# MotorBoardDev.net
KiCad netlist of a schematic drawn in EAGLE
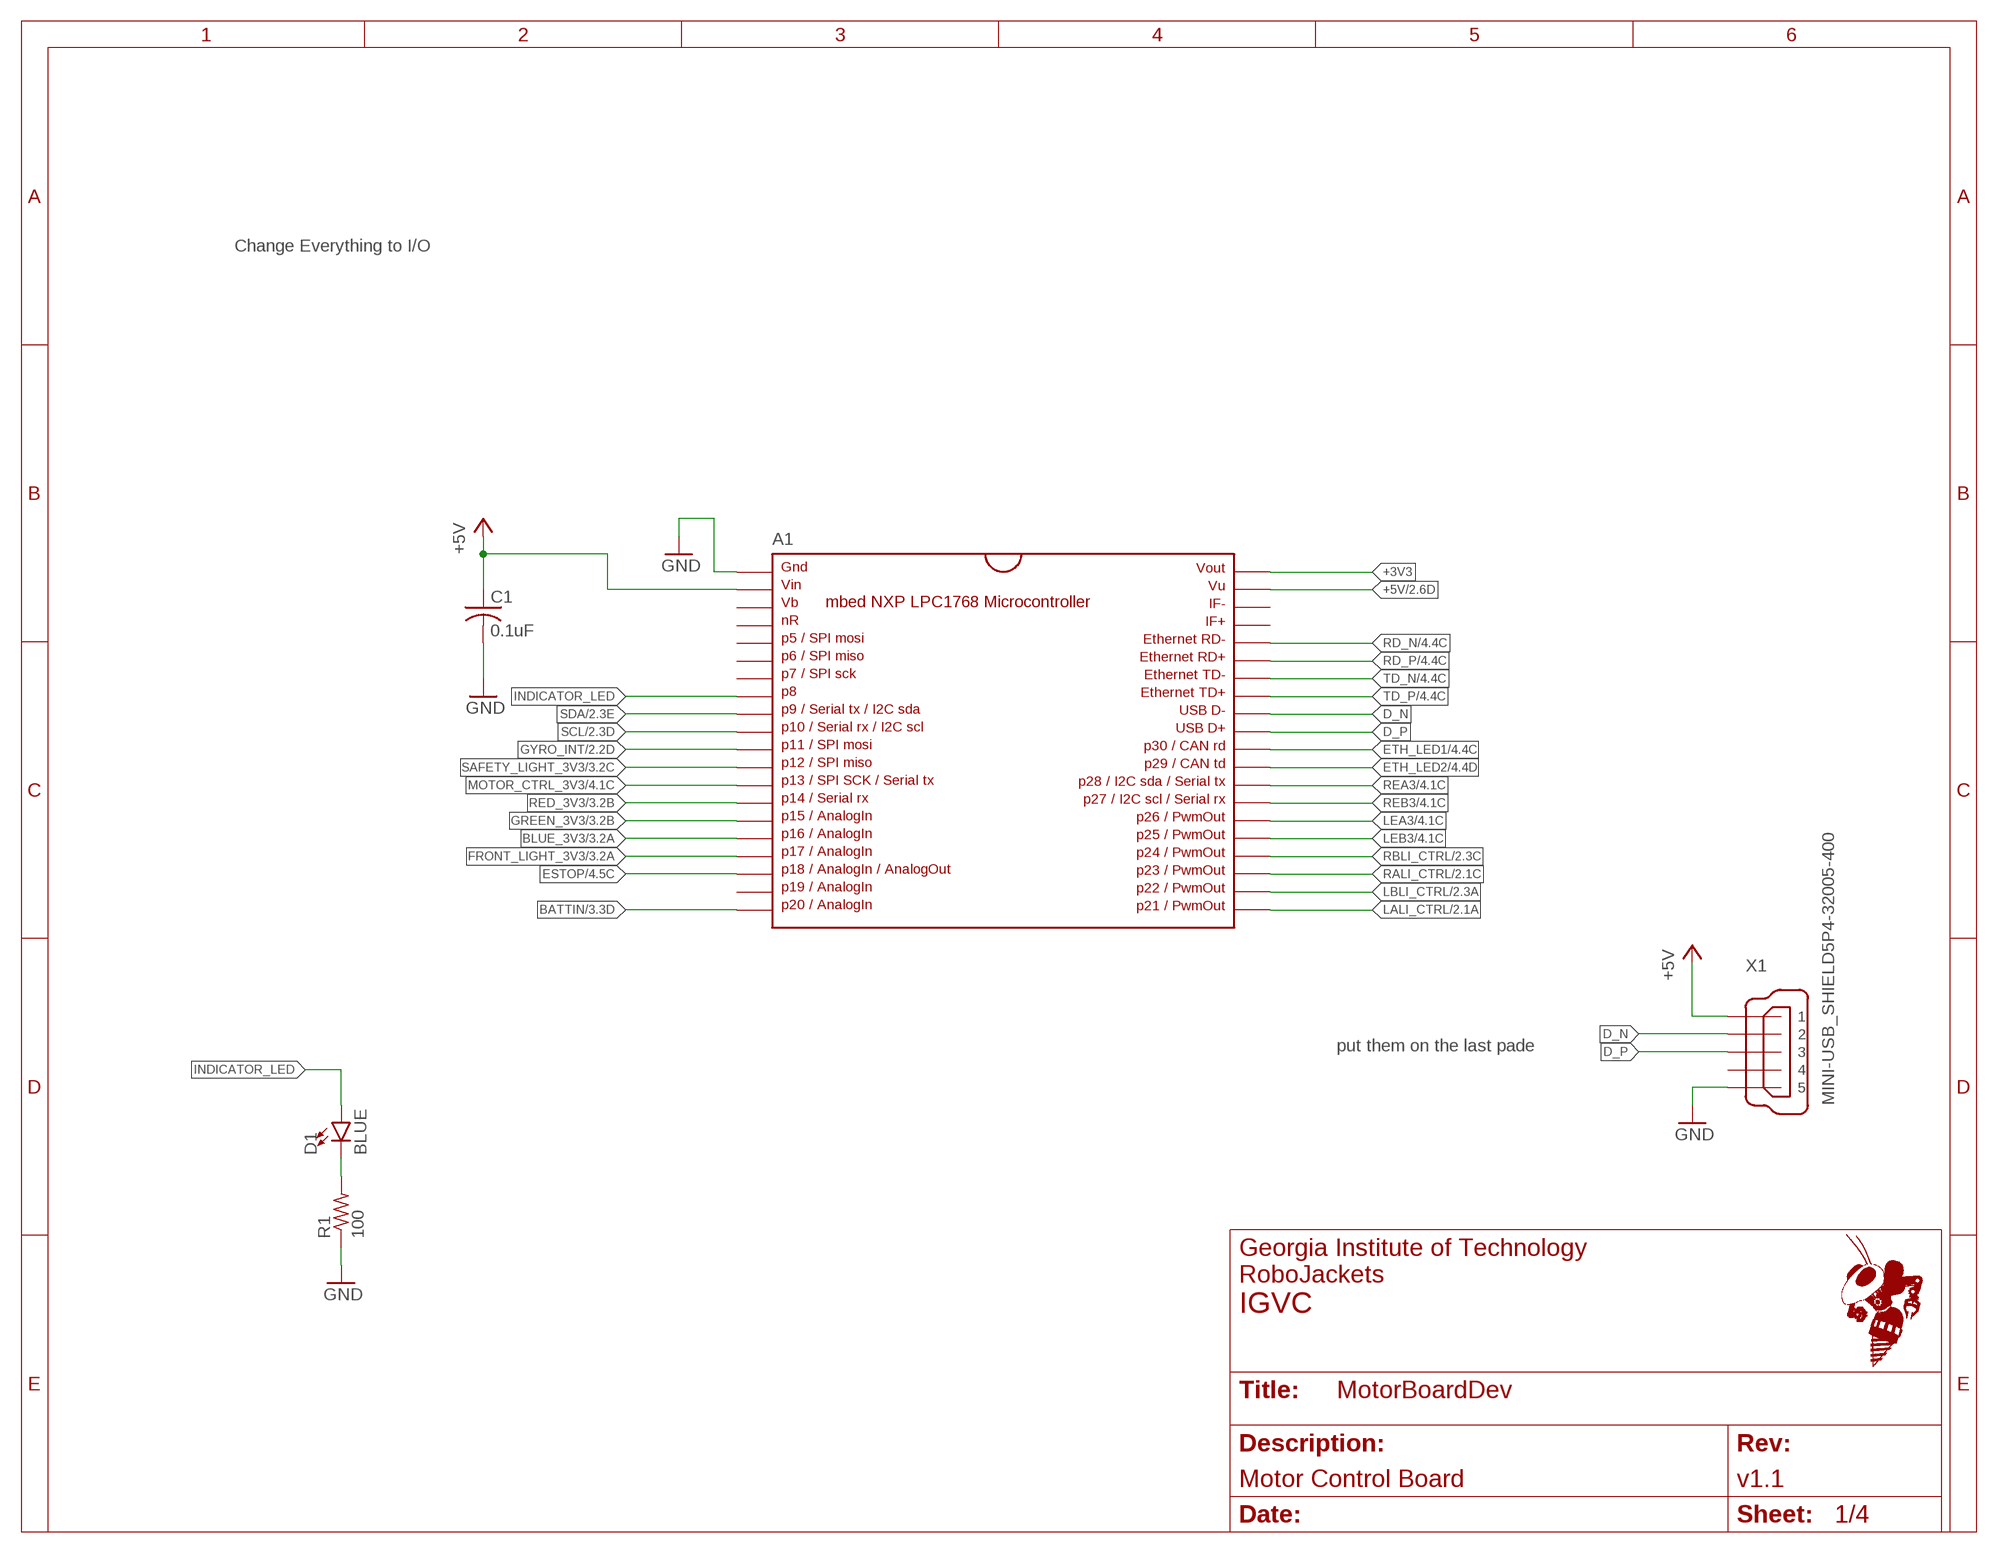
[diagram p0: schematic, sheet 1]
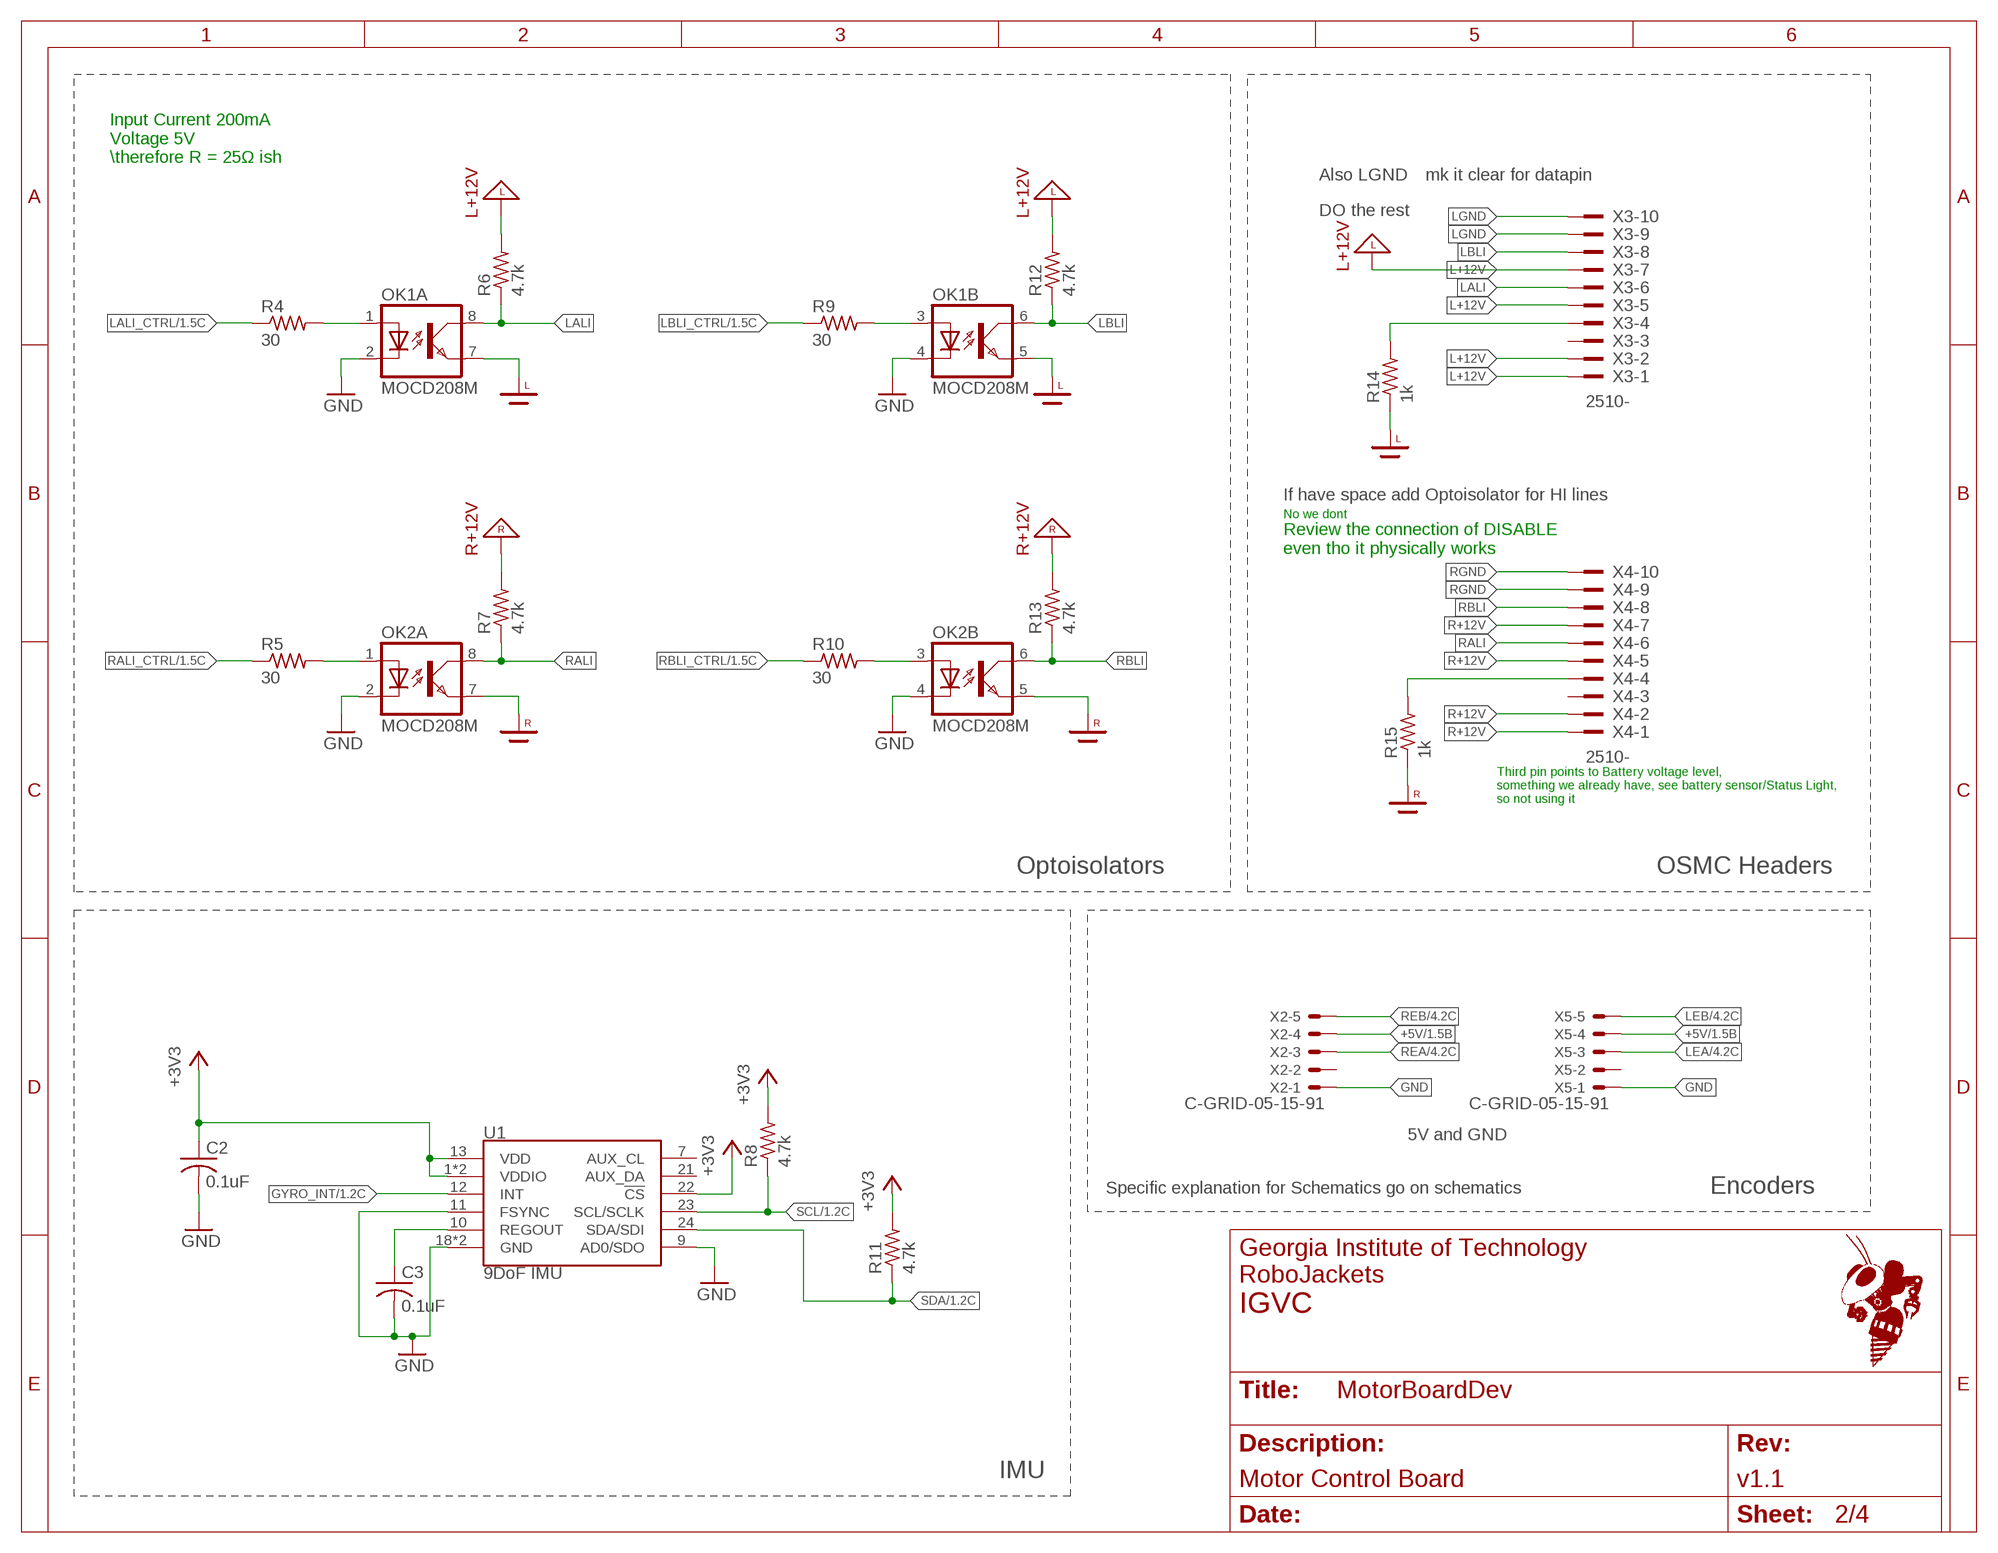
[diagram p1: schematic, sheet 2]
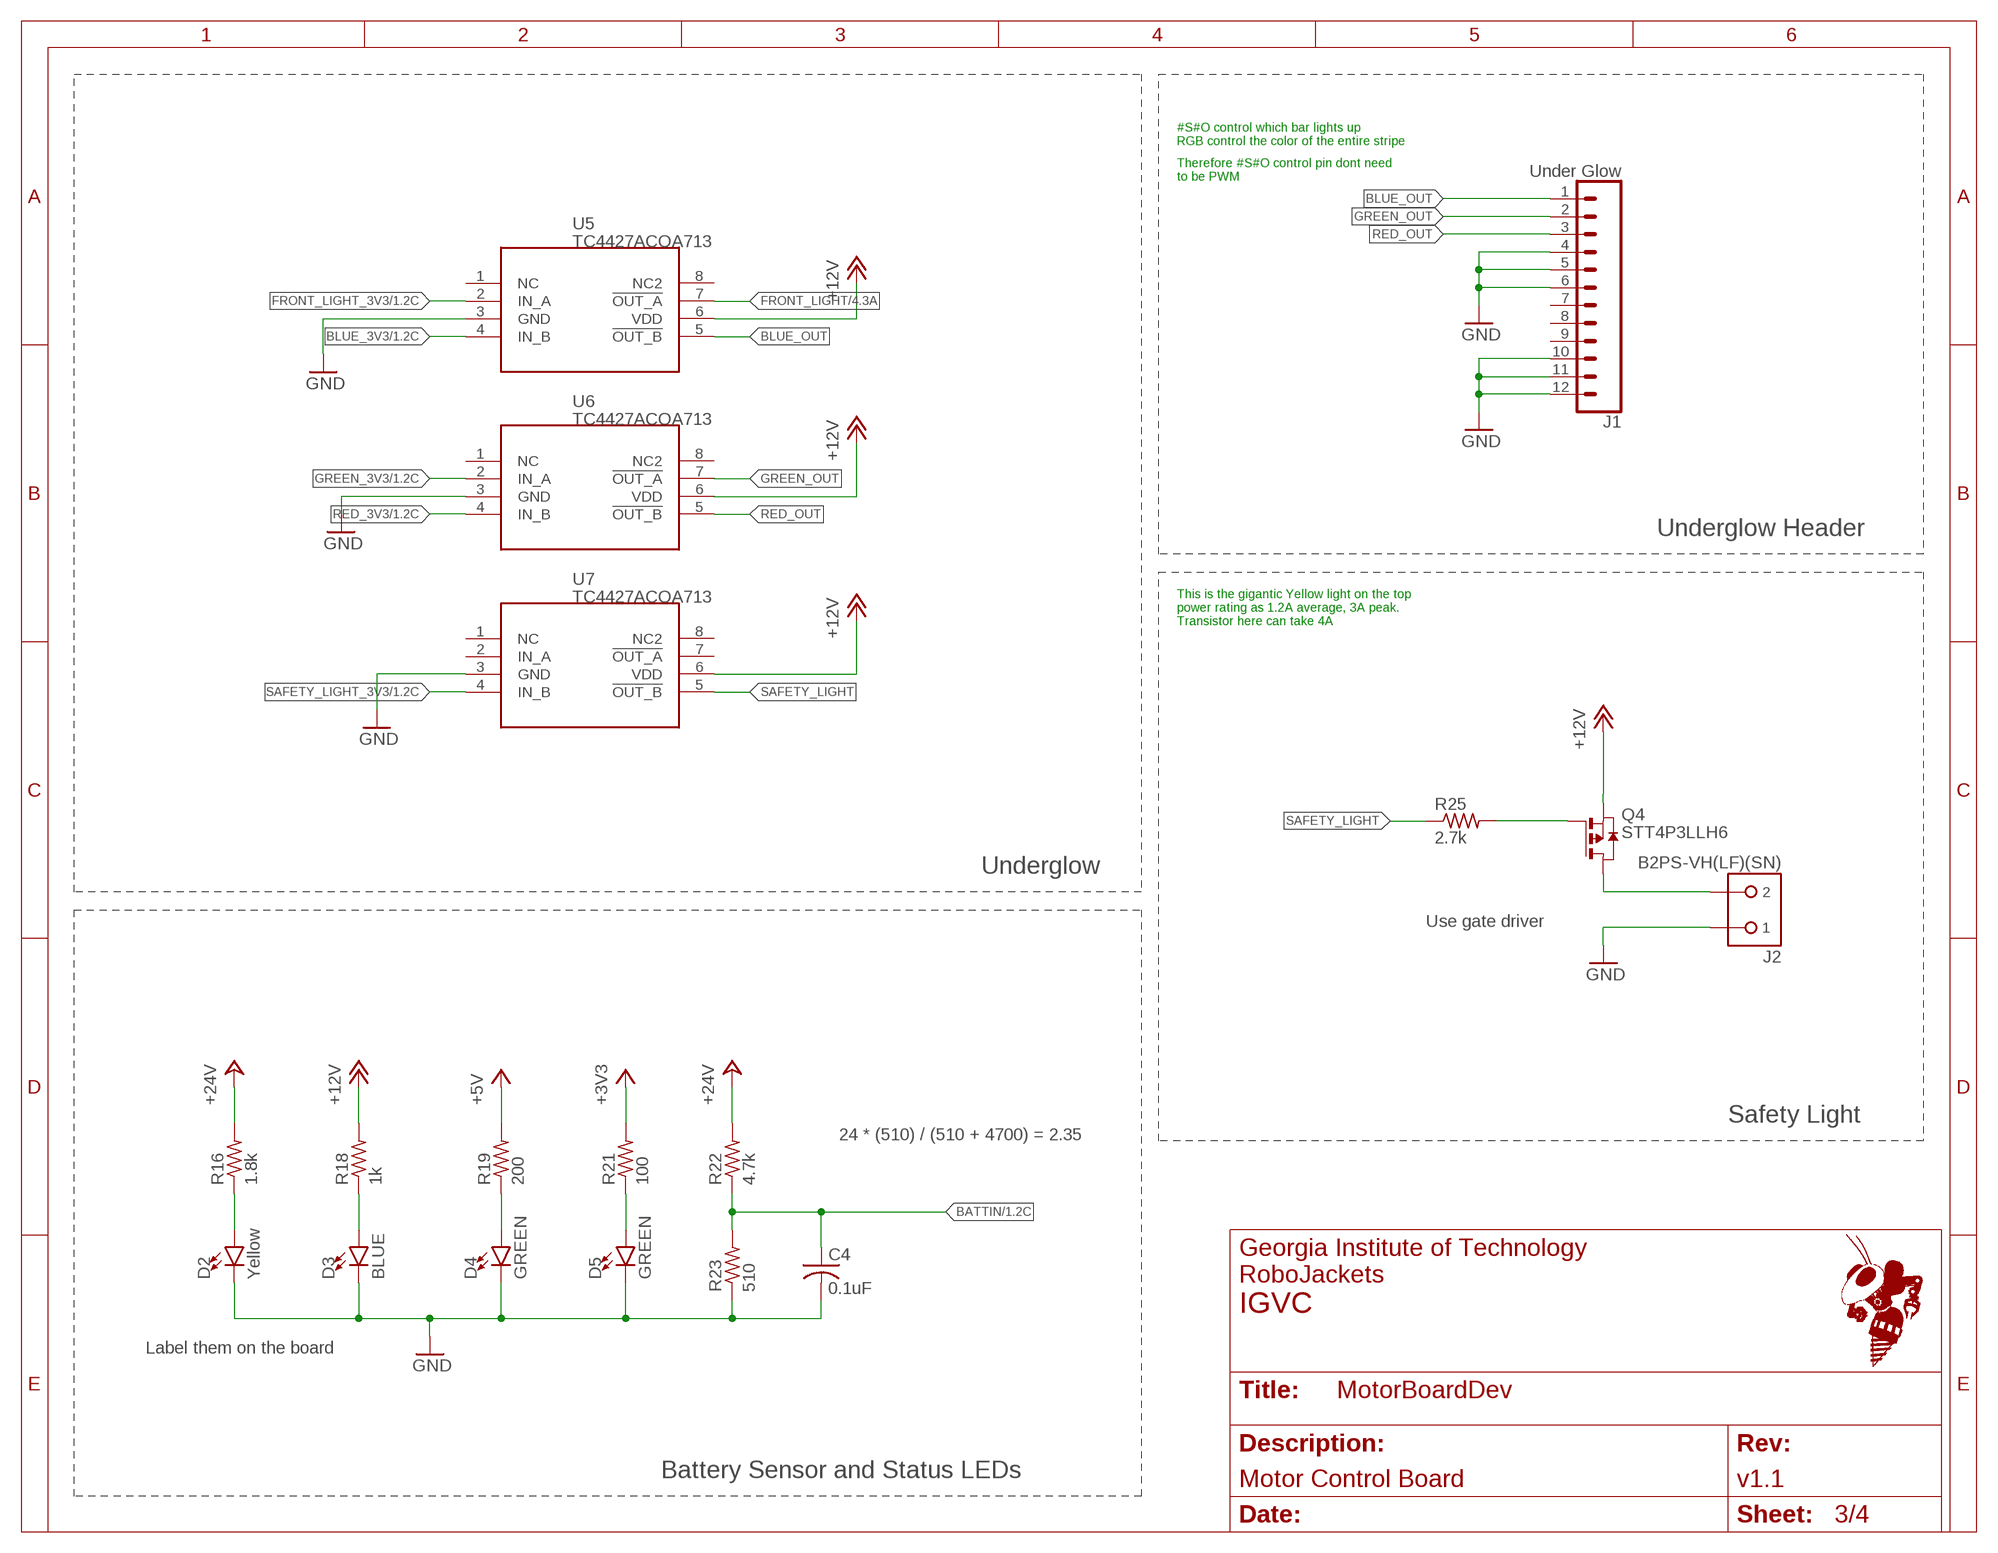
[diagram p2: schematic, sheet 3]
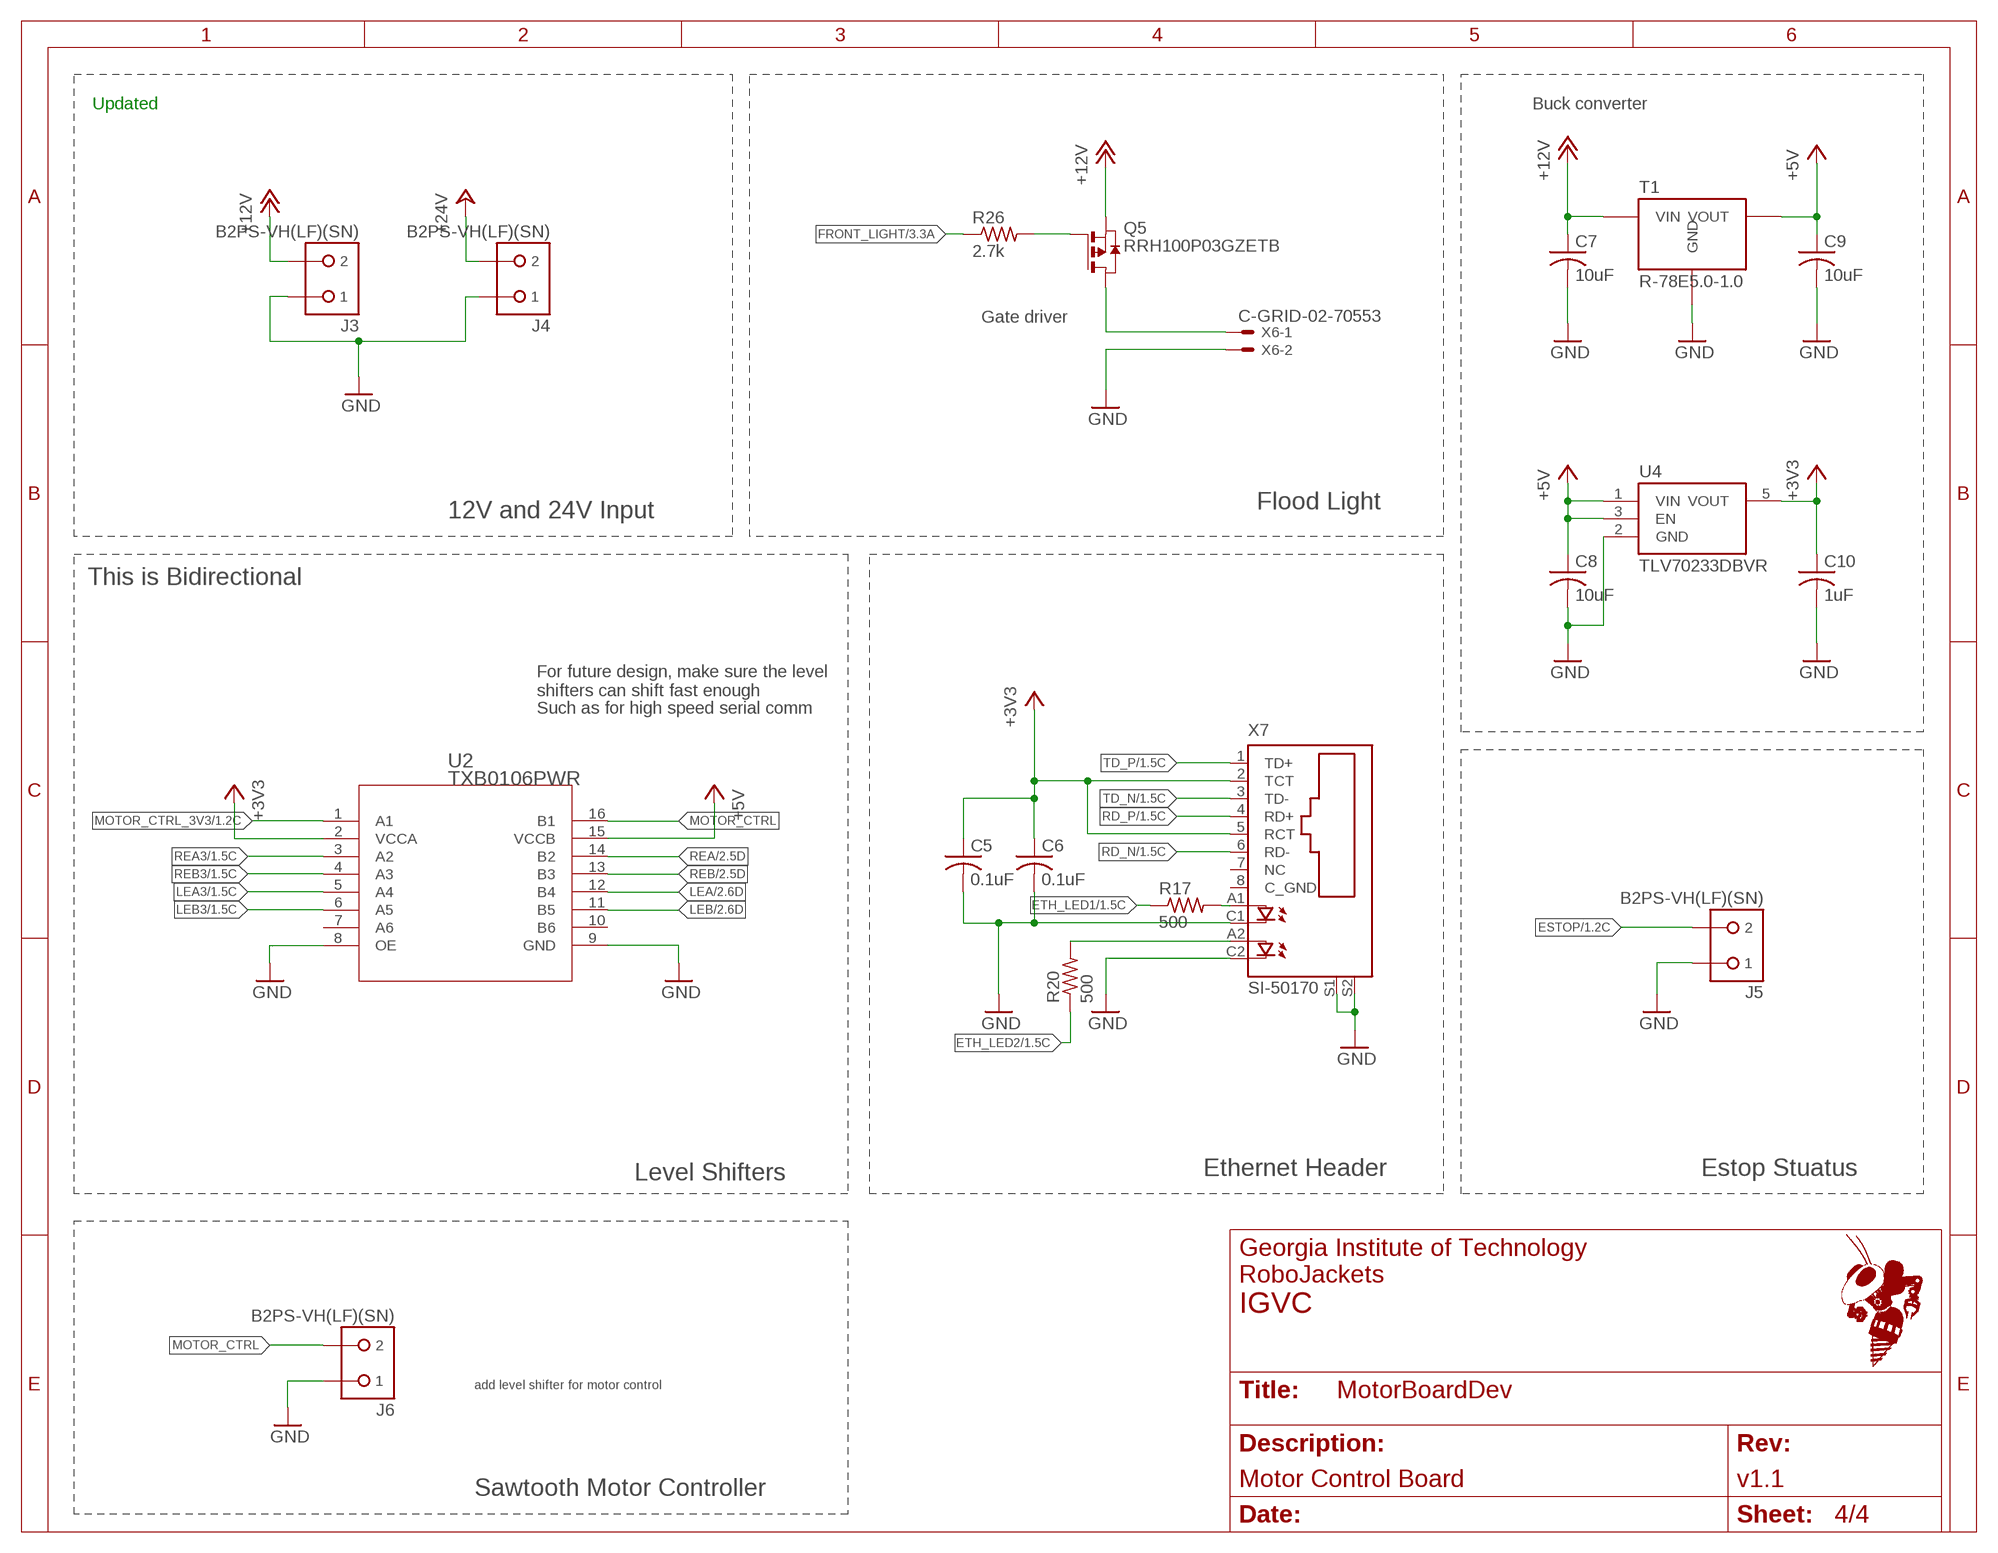
[diagram p3: schematic, sheet 4]

(export (version "E")
  (design (tool "Eeschema 10.0.6"))
  (components
    (comp (ref "A1")
      (value "MBED1768")
      (footprint "eagle-import:SPARKFUN-BOARDS_DIL40_0.9")
      (libsource (lib "eagle-import") (part "SPARKFUN-BOARDS_MBED_NXP_LPC1768"))
    )
    (comp (ref "C1")
      (value "0.1uF")
      (footprint "eagle-import:C0603")
      (libsource (lib "eagle-import") (part "C-USC0603"))
    )
    (comp (ref "D1")
      (value "BLUE")
      (footprint "eagle-import:LED-0603")
      (libsource (lib "eagle-import") (part "LED-BLUE0603"))
    )
    (comp (ref "R1")
      (value "100")
      (footprint "eagle-import:R0603")
      (libsource (lib "eagle-import") (part "R-US_R0603"))
    )
    (comp (ref "X1")
      (value "MINI-USB_SHIELD5P4-32005-400")
      (footprint "eagle-import:32005-400")
      (libsource (lib "eagle-import") (part "MINI-USB_SHIELD5P4-32005-400"))
    )
    (comp (ref "C2")
      (value "0.1uF")
      (footprint "eagle-import:C0603")
      (libsource (lib "eagle-import") (part "C-USC0603"))
    )
    (comp (ref "C3")
      (value "0.1uF")
      (footprint "eagle-import:C0603")
      (libsource (lib "eagle-import") (part "C-USC0603"))
    )
    (comp (ref "OK1")
      (value "MOCD208M")
      (footprint "eagle-import:SOIC08-FAIRCHILD")
      (fields (field (name "MF") "FAIRCHILD SEMICONDUCTOR"))
      (libsource (lib "eagle-import") (part "MOCD20M8"))
    )
    (comp (ref "OK2")
      (value "MOCD208M")
      (footprint "eagle-import:SOIC08-FAIRCHILD")
      (fields (field (name "MF") "FAIRCHILD SEMICONDUCTOR"))
      (libsource (lib "eagle-import") (part "MOCD20M8"))
    )
    (comp (ref "R4")
      (value "30")
      (footprint "eagle-import:R0603")
      (libsource (lib "eagle-import") (part "R-US_R0603"))
    )
    (comp (ref "R5")
      (value "30")
      (footprint "eagle-import:R0603")
      (libsource (lib "eagle-import") (part "R-US_R0603"))
    )
    (comp (ref "R6")
      (value "4.7k")
      (footprint "eagle-import:R0603")
      (libsource (lib "eagle-import") (part "R-US_R0603"))
    )
    (comp (ref "R7")
      (value "4.7k")
      (footprint "eagle-import:R0603")
      (libsource (lib "eagle-import") (part "R-US_R0603"))
    )
    (comp (ref "R8")
      (value "4.7k")
      (footprint "eagle-import:R0603")
      (libsource (lib "eagle-import") (part "R-US_R0603"))
    )
    (comp (ref "R9")
      (value "30")
      (footprint "eagle-import:R0603")
      (libsource (lib "eagle-import") (part "R-US_R0603"))
    )
    (comp (ref "R10")
      (value "30")
      (footprint "eagle-import:R0603")
      (libsource (lib "eagle-import") (part "R-US_R0603"))
    )
    (comp (ref "R11")
      (value "4.7k")
      (footprint "eagle-import:R0603")
      (libsource (lib "eagle-import") (part "R-US_R0603"))
    )
    (comp (ref "R12")
      (value "4.7k")
      (footprint "eagle-import:R0603")
      (libsource (lib "eagle-import") (part "R-US_R0603"))
    )
    (comp (ref "R13")
      (value "4.7k")
      (footprint "eagle-import:R0603")
      (libsource (lib "eagle-import") (part "R-US_R0603"))
    )
    (comp (ref "R14")
      (value "1k")
      (footprint "eagle-import:R0603")
      (libsource (lib "eagle-import") (part "R-US_R0603"))
    )
    (comp (ref "R15")
      (value "1k")
      (footprint "eagle-import:R0603")
      (libsource (lib "eagle-import") (part "R-US_R0603"))
    )
    (comp (ref "U1")
      (value "9DoF IMU")
      (footprint "eagle-import:QFN24-3X3")
      (libsource (lib "eagle-import") (part "MPU-9250"))
    )
    (comp (ref "X2")
      (value "C-GRID-05-15-91")
      (footprint "eagle-import:15-91-05")
      (libsource (lib "eagle-import") (part "C-GRID-05-15-91"))
    )
    (comp (ref "X3")
      (value "2510-")
      (footprint "eagle-import:PAK100_2500-10")
      (fields (field (name "MF") "3M") (field (name "MPN") "2510-6002UB"))
      (libsource (lib "eagle-import") (part "2510-"))
    )
    (comp (ref "X4")
      (value "2510-")
      (footprint "eagle-import:PAK100_2500-10")
      (fields (field (name "MF") "3M") (field (name "MPN") "2510-6002UB"))
      (libsource (lib "eagle-import") (part "2510-"))
    )
    (comp (ref "X5")
      (value "C-GRID-05-15-91")
      (footprint "eagle-import:15-91-05")
      (libsource (lib "eagle-import") (part "C-GRID-05-15-91"))
    )
    (comp (ref "C5")
      (value "0.1uF")
      (footprint "eagle-import:C0603")
      (libsource (lib "eagle-import") (part "C-USC0603"))
    )
    (comp (ref "C6")
      (value "0.1uF")
      (footprint "eagle-import:C0603")
      (libsource (lib "eagle-import") (part "C-USC0603"))
    )
    (comp (ref "C7")
      (value "10uF")
      (footprint "eagle-import:C0805")
      (libsource (lib "eagle-import") (part "C-USC0805"))
    )
    (comp (ref "C8")
      (value "10uF")
      (footprint "eagle-import:C0805")
      (libsource (lib "eagle-import") (part "C-USC0805"))
    )
    (comp (ref "C9")
      (value "10uF")
      (footprint "eagle-import:C0805")
      (libsource (lib "eagle-import") (part "C-USC0805"))
    )
    (comp (ref "C10")
      (value "1uF")
      (footprint "eagle-import:C0805")
      (libsource (lib "eagle-import") (part "C-USC0805"))
    )
    (comp (ref "J3")
      (value "B2PS-VH(LF)(SN)")
      (footprint "eagle-import:B2PS-CENTERED")
      (libsource (lib "eagle-import") (part "B2P?-VH(LF)(SN)S"))
    )
    (comp (ref "J4")
      (value "B2PS-VH(LF)(SN)")
      (footprint "eagle-import:B2PS-CENTERED")
      (libsource (lib "eagle-import") (part "B2P?-VH(LF)(SN)S"))
    )
    (comp (ref "J5")
      (value "B2PS-VH(LF)(SN)")
      (footprint "eagle-import:B2PS-CENTERED")
      (libsource (lib "eagle-import") (part "B2P?-VH(LF)(SN)S"))
    )
    (comp (ref "J6")
      (value "B2PS-VH(LF)(SN)")
      (footprint "eagle-import:B2PS-CENTERED")
      (libsource (lib "eagle-import") (part "B2P?-VH(LF)(SN)S"))
    )
    (comp (ref "Q5")
      (value "RRH100P03GZETB")
      (footprint "eagle-import:SOIC-8")
      (libsource (lib "eagle-import") (part "RRH100P03GZETB"))
    )
    (comp (ref "R17")
      (value "500")
      (footprint "eagle-import:R0603")
      (libsource (lib "eagle-import") (part "R-US_R0603"))
    )
    (comp (ref "R20")
      (value "500")
      (footprint "eagle-import:R0603")
      (libsource (lib "eagle-import") (part "R-US_R0603"))
    )
    (comp (ref "R26")
      (value "2.7k")
      (footprint "eagle-import:R0603")
      (libsource (lib "eagle-import") (part "R-US_R0603"))
    )
    (comp (ref "T1")
      (value "R-78E5.0-1.0")
      (footprint "eagle-import:R-78E")
      (libsource (lib "eagle-import") (part "R-78E5.0-1.0"))
    )
    (comp (ref "U2")
      (value "TXB0106PWR")
      (footprint "eagle-import:PW16")
      (libsource (lib "eagle-import") (part "TXB0106PWR"))
    )
    (comp (ref "U4")
      (value "TLV70233DBVR")
      (footprint "eagle-import:SOT-23-5")
      (libsource (lib "eagle-import") (part "TLV70233DBVR"))
    )
    (comp (ref "X6")
      (value "C-GRID-02-70553")
      (footprint "eagle-import:70553-02")
      (libsource (lib "eagle-import") (part "C-GRID-02-70553"))
    )
    (comp (ref "X7")
      (value "SI-50170")
      (footprint "eagle-import:SI-50170")
      (libsource (lib "eagle-import") (part "SI-50170"))
    )
    (comp (ref "C4")
      (value "0.1uF")
      (footprint "eagle-import:C0603")
      (libsource (lib "eagle-import") (part "C-USC0603"))
    )
    (comp (ref "D2")
      (value "Yellow")
      (footprint "eagle-import:LED-0603")
      (libsource (lib "eagle-import") (part "LED-YELLOW0603"))
    )
    (comp (ref "D3")
      (value "BLUE")
      (footprint "eagle-import:LED-0603")
      (libsource (lib "eagle-import") (part "LED-BLUE0603"))
    )
    (comp (ref "D4")
      (value "GREEN")
      (footprint "eagle-import:LED-0603")
      (libsource (lib "eagle-import") (part "LED-GREEN0603"))
    )
    (comp (ref "D5")
      (value "GREEN")
      (footprint "eagle-import:LED-0603")
      (libsource (lib "eagle-import") (part "LED-GREEN0603"))
    )
    (comp (ref "J1")
      (value "Under Glow")
      (footprint "eagle-import:1X12_LOCK_LONGPADS")
      (libsource (lib "eagle-import") (part "CONN_12LOCK_LONGPADS"))
    )
    (comp (ref "J2")
      (value "B2PS-VH(LF)(SN)")
      (footprint "eagle-import:B2PS-CENTERED")
      (libsource (lib "eagle-import") (part "B2P?-VH(LF)(SN)S"))
    )
    (comp (ref "Q4")
      (value "STT4P3LLH6")
      (footprint "eagle-import:SOT23-6")
      (libsource (lib "eagle-import") (part "STT4P3LLH6"))
    )
    (comp (ref "R16")
      (value "1.8k")
      (footprint "eagle-import:R0603")
      (libsource (lib "eagle-import") (part "R-US_R0603"))
    )
    (comp (ref "R18")
      (value "1k")
      (footprint "eagle-import:R0603")
      (libsource (lib "eagle-import") (part "R-US_R0603"))
    )
    (comp (ref "R19")
      (value "200")
      (footprint "eagle-import:R0603")
      (libsource (lib "eagle-import") (part "R-US_R0603"))
    )
    (comp (ref "R21")
      (value "100")
      (footprint "eagle-import:R0603")
      (libsource (lib "eagle-import") (part "R-US_R0603"))
    )
    (comp (ref "R22")
      (value "4.7k")
      (footprint "eagle-import:R0603")
      (libsource (lib "eagle-import") (part "R-US_R0603"))
    )
    (comp (ref "R23")
      (value "510")
      (footprint "eagle-import:R0603")
      (libsource (lib "eagle-import") (part "R-US_R0603"))
    )
    (comp (ref "R25")
      (value "2.7k")
      (footprint "eagle-import:R0603")
      (libsource (lib "eagle-import") (part "R-US_R0603"))
    )
    (comp (ref "U5")
      (value "TC4427ACOA713")
      (footprint "eagle-import:SOIC-8")
      (libsource (lib "eagle-import") (part "TC4427ACOA713"))
    )
    (comp (ref "U6")
      (value "TC4427ACOA713")
      (footprint "eagle-import:SOIC-8")
      (libsource (lib "eagle-import") (part "TC4427ACOA713"))
    )
    (comp (ref "U7")
      (value "TC4427ACOA713")
      (footprint "eagle-import:SOIC-8")
      (libsource (lib "eagle-import") (part "TC4427ACOA713"))
    )
  )
  (nets
    (net (code "1") (name "+3V3") (class "Default")
      (node (ref "A1") (pin "40") (pinfunction "P$40_40") (pintype "bidirectional"))
      (node (ref "C10") (pin "1") (pinfunction "1_1") (pintype "passive"))
      (node (ref "C2") (pin "1") (pinfunction "1_1") (pintype "passive"))
      (node (ref "C5") (pin "1") (pinfunction "1_1") (pintype "passive"))
      (node (ref "C6") (pin "1") (pinfunction "1_1") (pintype "passive"))
      (node (ref "R11") (pin "2") (pinfunction "2_2") (pintype "passive"))
      (node (ref "R21") (pin "2") (pinfunction "2_2") (pintype "passive"))
      (node (ref "R8") (pin "2") (pinfunction "2_2") (pintype "passive"))
      (node (ref "U1") (pin "1") (pinfunction "VDDIO_1") (pintype "bidirectional"))
      (node (ref "U1") (pin "13") (pinfunction "VDD_13") (pintype "bidirectional"))
      (node (ref "U1") (pin "22") (pinfunction "~{CS}_22") (pintype "bidirectional"))
      (node (ref "U1") (pin "8") (pinfunction "VDDIO_8") (pintype "bidirectional"))
      (node (ref "U2") (pin "2") (pinfunction "VCCA_2") (pintype "power_in"))
      (node (ref "U4") (pin "5") (pinfunction "VOUT_5") (pintype "bidirectional"))
      (node (ref "X7") (pin "2") (pinfunction "TCT_2") (pintype "passive"))
      (node (ref "X7") (pin "5") (pinfunction "RCT_5") (pintype "passive"))
    )
    (net (code "2") (name "+5V") (class "Default")
      (node (ref "A1") (pin "2") (pinfunction "P$2_2") (pintype "bidirectional"))
      (node (ref "A1") (pin "39") (pinfunction "P$39_39") (pintype "bidirectional"))
      (node (ref "C1") (pin "1") (pinfunction "1_1") (pintype "passive"))
      (node (ref "C8") (pin "1") (pinfunction "1_1") (pintype "passive"))
      (node (ref "C9") (pin "1") (pinfunction "1_1") (pintype "passive"))
      (node (ref "R19") (pin "2") (pinfunction "2_2") (pintype "passive"))
      (node (ref "T1") (pin "3") (pinfunction "VOUT_3") (pintype "bidirectional"))
      (node (ref "U2") (pin "15") (pinfunction "VCCB_15") (pintype "power_in"))
      (node (ref "U4") (pin "1") (pinfunction "VIN_1") (pintype "bidirectional"))
      (node (ref "U4") (pin "3") (pinfunction "EN_3") (pintype "bidirectional"))
      (node (ref "X1") (pin "1") (pinfunction "1_1") (pintype "passive"))
      (node (ref "X2") (pin "4") (pinfunction "S_4") (pintype "passive"))
      (node (ref "X5") (pin "4") (pinfunction "S_4") (pintype "passive"))
    )
    (net (code "3") (name "+12V") (class "Default")
      (node (ref "C7") (pin "1") (pinfunction "1_1") (pintype "passive"))
      (node (ref "J3") (pin "2") (pinfunction "2_2") (pintype "bidirectional"))
      (node (ref "Q4") (pin "4") (pinfunction "S_4") (pintype "passive"))
      (node (ref "Q5") (pin "1") (pinfunction "S_1") (pintype "passive"))
      (node (ref "Q5") (pin "2") (pinfunction "S_2") (pintype "passive"))
      (node (ref "Q5") (pin "3") (pinfunction "S_3") (pintype "passive"))
      (node (ref "R18") (pin "2") (pinfunction "2_2") (pintype "passive"))
      (node (ref "T1") (pin "1") (pinfunction "VIN_1") (pintype "bidirectional"))
      (node (ref "U5") (pin "6") (pinfunction "VDD_6") (pintype "bidirectional"))
      (node (ref "U6") (pin "6") (pinfunction "VDD_6") (pintype "bidirectional"))
      (node (ref "U7") (pin "6") (pinfunction "VDD_6") (pintype "bidirectional"))
    )
    (net (code "4") (name "+24V") (class "Default")
      (node (ref "J4") (pin "2") (pinfunction "2_2") (pintype "bidirectional"))
      (node (ref "R16") (pin "2") (pinfunction "2_2") (pintype "passive"))
      (node (ref "R22") (pin "2") (pinfunction "2_2") (pintype "passive"))
    )
    (net (code "5") (name "BATTIN") (class "Default")
      (node (ref "A1") (pin "20") (pinfunction "P$20_20") (pintype "bidirectional"))
      (node (ref "C4") (pin "1") (pinfunction "1_1") (pintype "passive"))
      (node (ref "R22") (pin "1") (pinfunction "1_1") (pintype "passive"))
      (node (ref "R23") (pin "2") (pinfunction "2_2") (pintype "passive"))
    )
    (net (code "6") (name "BLUE_3V3") (class "Default")
      (node (ref "A1") (pin "16") (pinfunction "P$16_16") (pintype "bidirectional"))
      (node (ref "U5") (pin "4") (pinfunction "IN_B_4") (pintype "bidirectional"))
    )
    (net (code "7") (name "BLUE_OUT") (class "Default")
      (node (ref "J1") (pin "1") (pinfunction "1_1") (pintype "passive"))
      (node (ref "U5") (pin "5") (pinfunction "~{OUT_B}_5") (pintype "bidirectional"))
    )
    (net (code "8") (name "D_N") (class "Default")
      (node (ref "A1") (pin "32") (pinfunction "P$32_32") (pintype "bidirectional"))
      (node (ref "X1") (pin "2") (pinfunction "2_2") (pintype "passive"))
    )
    (net (code "9") (name "D_P") (class "Default")
      (node (ref "A1") (pin "31") (pinfunction "P$31_31") (pintype "bidirectional"))
      (node (ref "X1") (pin "3") (pinfunction "3_3") (pintype "passive"))
    )
    (net (code "10") (name "ESTOP") (class "Default")
      (node (ref "A1") (pin "18") (pinfunction "P$18_18") (pintype "bidirectional"))
      (node (ref "J5") (pin "2") (pinfunction "2_2") (pintype "bidirectional"))
    )
    (net (code "11") (name "ETH_LED1") (class "Default")
      (node (ref "A1") (pin "30") (pinfunction "P$30_30") (pintype "bidirectional"))
      (node (ref "R17") (pin "1") (pinfunction "1_1") (pintype "passive"))
    )
    (net (code "12") (name "ETH_LED2") (class "Default")
      (node (ref "A1") (pin "29") (pinfunction "P$29_29") (pintype "bidirectional"))
      (node (ref "R20") (pin "1") (pinfunction "1_1") (pintype "passive"))
    )
    (net (code "13") (name "FRONT_LIGHT") (class "Default")
      (node (ref "R26") (pin "1") (pinfunction "1_1") (pintype "passive"))
      (node (ref "U5") (pin "7") (pinfunction "~{OUT_A}_7") (pintype "bidirectional"))
    )
    (net (code "14") (name "FRONT_LIGHT_3V3") (class "Default")
      (node (ref "A1") (pin "17") (pinfunction "P$17_17") (pintype "bidirectional"))
      (node (ref "U5") (pin "2") (pinfunction "IN_A_2") (pintype "bidirectional"))
    )
    (net (code "15") (name "GND") (class "Default")
      (node (ref "A1") (pin "1") (pinfunction "P$1_1") (pintype "bidirectional"))
      (node (ref "C1") (pin "2") (pinfunction "2_2") (pintype "passive"))
      (node (ref "C10") (pin "2") (pinfunction "2_2") (pintype "passive"))
      (node (ref "C2") (pin "2") (pinfunction "2_2") (pintype "passive"))
      (node (ref "C3") (pin "2") (pinfunction "2_2") (pintype "passive"))
      (node (ref "C4") (pin "2") (pinfunction "2_2") (pintype "passive"))
      (node (ref "C5") (pin "2") (pinfunction "2_2") (pintype "passive"))
      (node (ref "C6") (pin "2") (pinfunction "2_2") (pintype "passive"))
      (node (ref "C7") (pin "2") (pinfunction "2_2") (pintype "passive"))
      (node (ref "C8") (pin "2") (pinfunction "2_2") (pintype "passive"))
      (node (ref "C9") (pin "2") (pinfunction "2_2") (pintype "passive"))
      (node (ref "D2") (pin "C") (pinfunction "C_C") (pintype "passive"))
      (node (ref "D3") (pin "C") (pinfunction "C_C") (pintype "passive"))
      (node (ref "D4") (pin "C") (pinfunction "C_C") (pintype "passive"))
      (node (ref "D5") (pin "C") (pinfunction "C_C") (pintype "passive"))
      (node (ref "J1") (pin "10") (pinfunction "10_10") (pintype "passive"))
      (node (ref "J1") (pin "11") (pinfunction "11_11") (pintype "passive"))
      (node (ref "J1") (pin "12") (pinfunction "12_12") (pintype "passive"))
      (node (ref "J1") (pin "4") (pinfunction "4_4") (pintype "passive"))
      (node (ref "J1") (pin "5") (pinfunction "5_5") (pintype "passive"))
      (node (ref "J1") (pin "6") (pinfunction "6_6") (pintype "passive"))
      (node (ref "J2") (pin "1") (pinfunction "1_1") (pintype "bidirectional"))
      (node (ref "J3") (pin "1") (pinfunction "1_1") (pintype "bidirectional"))
      (node (ref "J4") (pin "1") (pinfunction "1_1") (pintype "bidirectional"))
      (node (ref "J5") (pin "1") (pinfunction "1_1") (pintype "bidirectional"))
      (node (ref "J6") (pin "1") (pinfunction "1_1") (pintype "bidirectional"))
      (node (ref "OK1") (pin "2") (pinfunction "C_2") (pintype "passive"))
      (node (ref "OK1") (pin "4") (pinfunction "C_4") (pintype "passive"))
      (node (ref "OK2") (pin "2") (pinfunction "C_2") (pintype "passive"))
      (node (ref "OK2") (pin "4") (pinfunction "C_4") (pintype "passive"))
      (node (ref "R1") (pin "1") (pinfunction "1_1") (pintype "passive"))
      (node (ref "R23") (pin "1") (pinfunction "1_1") (pintype "passive"))
      (node (ref "T1") (pin "2") (pinfunction "GND_2") (pintype "bidirectional"))
      (node (ref "U1") (pin "11") (pinfunction "FSYNC_11") (pintype "bidirectional"))
      (node (ref "U1") (pin "18") (pinfunction "GND_18") (pintype "bidirectional"))
      (node (ref "U1") (pin "20") (pinfunction "GND_20") (pintype "bidirectional"))
      (node (ref "U1") (pin "9") (pinfunction "AD0/SDO_9") (pintype "bidirectional"))
      (node (ref "U2") (pin "8") (pinfunction "OE_8") (pintype "output"))
      (node (ref "U2") (pin "9") (pinfunction "GND_9") (pintype "power_in"))
      (node (ref "U4") (pin "2") (pinfunction "GND_2") (pintype "bidirectional"))
      (node (ref "U5") (pin "3") (pinfunction "GND_3") (pintype "bidirectional"))
      (node (ref "U6") (pin "3") (pinfunction "GND_3") (pintype "bidirectional"))
      (node (ref "U7") (pin "3") (pinfunction "GND_3") (pintype "bidirectional"))
      (node (ref "X1") (pin "5") (pinfunction "5_5") (pintype "passive"))
      (node (ref "X2") (pin "1") (pinfunction "S_1") (pintype "passive"))
      (node (ref "X5") (pin "1") (pinfunction "S_1") (pintype "passive"))
      (node (ref "X6") (pin "2") (pinfunction "S_2") (pintype "passive"))
      (node (ref "X7") (pin "C1") (pinfunction "C_C1") (pintype "passive"))
      (node (ref "X7") (pin "C2") (pinfunction "C1_C2") (pintype "passive"))
      (node (ref "X7") (pin "S1") (pinfunction "S1_S1") (pintype "passive"))
      (node (ref "X7") (pin "S2") (pinfunction "S2_S2") (pintype "passive"))
    )
    (net (code "16") (name "GREEN_3V3") (class "Default")
      (node (ref "A1") (pin "15") (pinfunction "P$15_15") (pintype "bidirectional"))
      (node (ref "U6") (pin "2") (pinfunction "IN_A_2") (pintype "bidirectional"))
    )
    (net (code "17") (name "GREEN_OUT") (class "Default")
      (node (ref "J1") (pin "2") (pinfunction "2_2") (pintype "passive"))
      (node (ref "U6") (pin "7") (pinfunction "~{OUT_A}_7") (pintype "bidirectional"))
    )
    (net (code "18") (name "GYRO_INT") (class "Default")
      (node (ref "A1") (pin "11") (pinfunction "P$11_11") (pintype "bidirectional"))
      (node (ref "U1") (pin "12") (pinfunction "INT_12") (pintype "bidirectional"))
    )
    (net (code "19") (name "INDICATOR_LED") (class "Default")
      (node (ref "A1") (pin "8") (pinfunction "P$8_8") (pintype "bidirectional"))
      (node (ref "D1") (pin "A") (pinfunction "A_A") (pintype "passive"))
    )
    (net (code "20") (name "L+12V") (class "Default")
      (node (ref "R12") (pin "2") (pinfunction "2_2") (pintype "passive"))
      (node (ref "R6") (pin "2") (pinfunction "2_2") (pintype "passive"))
      (node (ref "X3") (pin "1") (pinfunction "KL_1") (pintype "passive"))
      (node (ref "X3") (pin "2") (pinfunction "KL_2") (pintype "passive"))
      (node (ref "X3") (pin "5") (pinfunction "KL_5") (pintype "passive"))
      (node (ref "X3") (pin "7") (pinfunction "KL_7") (pintype "passive"))
    )
    (net (code "21") (name "LALI") (class "Default")
      (node (ref "OK1") (pin "8") (pinfunction "COL_8") (pintype "passive"))
      (node (ref "R6") (pin "1") (pinfunction "1_1") (pintype "passive"))
      (node (ref "X3") (pin "6") (pinfunction "KL_6") (pintype "passive"))
    )
    (net (code "22") (name "LALI_CTRL") (class "Default")
      (node (ref "A1") (pin "21") (pinfunction "P$21_21") (pintype "bidirectional"))
      (node (ref "R4") (pin "1") (pinfunction "1_1") (pintype "passive"))
    )
    (net (code "23") (name "LBLI") (class "Default")
      (node (ref "OK1") (pin "6") (pinfunction "COL_6") (pintype "passive"))
      (node (ref "R12") (pin "1") (pinfunction "1_1") (pintype "passive"))
      (node (ref "X3") (pin "8") (pinfunction "KL_8") (pintype "passive"))
    )
    (net (code "24") (name "LBLI_CTRL") (class "Default")
      (node (ref "A1") (pin "22") (pinfunction "P$22_22") (pintype "bidirectional"))
      (node (ref "R9") (pin "1") (pinfunction "1_1") (pintype "passive"))
    )
    (net (code "25") (name "LEA") (class "Default")
      (node (ref "U2") (pin "12") (pinfunction "B4_12") (pintype "bidirectional"))
      (node (ref "X5") (pin "3") (pinfunction "S_3") (pintype "passive"))
    )
    (net (code "26") (name "LEA3") (class "Default")
      (node (ref "A1") (pin "26") (pinfunction "P$26_26") (pintype "bidirectional"))
      (node (ref "U2") (pin "5") (pinfunction "A4_5") (pintype "bidirectional"))
    )
    (net (code "27") (name "LEB") (class "Default")
      (node (ref "U2") (pin "11") (pinfunction "B5_11") (pintype "bidirectional"))
      (node (ref "X5") (pin "5") (pinfunction "S_5") (pintype "passive"))
    )
    (net (code "28") (name "LEB3") (class "Default")
      (node (ref "A1") (pin "25") (pinfunction "P$25_25") (pintype "bidirectional"))
      (node (ref "U2") (pin "6") (pinfunction "A5_6") (pintype "bidirectional"))
    )
    (net (code "29") (name "LGND") (class "Default")
      (node (ref "OK1") (pin "5") (pinfunction "EMIT_5") (pintype "passive"))
      (node (ref "OK1") (pin "7") (pinfunction "EMIT_7") (pintype "passive"))
      (node (ref "R14") (pin "1") (pinfunction "1_1") (pintype "passive"))
      (node (ref "X3") (pin "10") (pinfunction "KL_10") (pintype "passive"))
      (node (ref "X3") (pin "9") (pinfunction "KL_9") (pintype "passive"))
    )
    (net (code "30") (name "MOTOR_CTRL") (class "Default")
      (node (ref "J6") (pin "2") (pinfunction "2_2") (pintype "bidirectional"))
      (node (ref "U2") (pin "16") (pinfunction "B1_16") (pintype "bidirectional"))
    )
    (net (code "31") (name "MOTOR_CTRL_3V3") (class "Default")
      (node (ref "A1") (pin "13") (pinfunction "P$13_13") (pintype "bidirectional"))
      (node (ref "U2") (pin "1") (pinfunction "A1_1") (pintype "bidirectional"))
    )
    (net (code "32") (name "Net-(D1-PadC)") (class "Default")
      (node (ref "D1") (pin "C") (pinfunction "C_C") (pintype "passive"))
      (node (ref "R1") (pin "2") (pinfunction "2_2") (pintype "passive"))
    )
    (net (code "33") (name "Net-(D2-PadA)") (class "Default")
      (node (ref "D2") (pin "A") (pinfunction "A_A") (pintype "passive"))
      (node (ref "R16") (pin "1") (pinfunction "1_1") (pintype "passive"))
    )
    (net (code "34") (name "Net-(D3-PadA)") (class "Default")
      (node (ref "D3") (pin "A") (pinfunction "A_A") (pintype "passive"))
      (node (ref "R18") (pin "1") (pinfunction "1_1") (pintype "passive"))
    )
    (net (code "35") (name "Net-(D4-PadA)") (class "Default")
      (node (ref "D4") (pin "A") (pinfunction "A_A") (pintype "passive"))
      (node (ref "R19") (pin "1") (pinfunction "1_1") (pintype "passive"))
    )
    (net (code "36") (name "Net-(D5-PadA)") (class "Default")
      (node (ref "D5") (pin "A") (pinfunction "A_A") (pintype "passive"))
      (node (ref "R21") (pin "1") (pinfunction "1_1") (pintype "passive"))
    )
    (net (code "37") (name "Net-(J2-Pad2)") (class "Default")
      (node (ref "J2") (pin "2") (pinfunction "2_2") (pintype "bidirectional"))
      (node (ref "Q4") (pin "1") (pinfunction "D_1") (pintype "passive"))
      (node (ref "Q4") (pin "2") (pinfunction "D_2") (pintype "passive"))
      (node (ref "Q4") (pin "5") (pinfunction "D_5") (pintype "passive"))
      (node (ref "Q4") (pin "6") (pinfunction "D_6") (pintype "passive"))
    )
    (net (code "38") (name "Net-(OK1A-A)") (class "Default")
      (node (ref "OK1") (pin "1") (pinfunction "A_1") (pintype "passive"))
      (node (ref "R4") (pin "2") (pinfunction "2_2") (pintype "passive"))
    )
    (net (code "39") (name "Net-(OK1B-A)") (class "Default")
      (node (ref "OK1") (pin "3") (pinfunction "A_3") (pintype "passive"))
      (node (ref "R9") (pin "2") (pinfunction "2_2") (pintype "passive"))
    )
    (net (code "40") (name "Net-(OK2A-A)") (class "Default")
      (node (ref "OK2") (pin "1") (pinfunction "A_1") (pintype "passive"))
      (node (ref "R5") (pin "2") (pinfunction "2_2") (pintype "passive"))
    )
    (net (code "41") (name "Net-(OK2B-A)") (class "Default")
      (node (ref "OK2") (pin "3") (pinfunction "A_3") (pintype "passive"))
      (node (ref "R10") (pin "2") (pinfunction "2_2") (pintype "passive"))
    )
    (net (code "42") (name "Net-(Q4-G)") (class "Default")
      (node (ref "Q4") (pin "3") (pinfunction "G_3") (pintype "passive"))
      (node (ref "R25") (pin "2") (pinfunction "2_2") (pintype "passive"))
    )
    (net (code "43") (name "Net-(Q5-G)") (class "Default")
      (node (ref "Q5") (pin "4") (pinfunction "G_4") (pintype "passive"))
      (node (ref "R26") (pin "2") (pinfunction "2_2") (pintype "passive"))
    )
    (net (code "44") (name "Net-(U1-REGOUT)") (class "Default")
      (node (ref "C3") (pin "1") (pinfunction "1_1") (pintype "passive"))
      (node (ref "U1") (pin "10") (pinfunction "REGOUT_10") (pintype "bidirectional"))
    )
    (net (code "45") (name "Net-(X3E-KL)") (class "Default")
      (node (ref "R14") (pin "2") (pinfunction "2_2") (pintype "passive"))
      (node (ref "X3") (pin "4") (pinfunction "KL_4") (pintype "passive"))
    )
    (net (code "46") (name "Net-(X4E-KL)") (class "Default")
      (node (ref "R15") (pin "2") (pinfunction "2_2") (pintype "passive"))
      (node (ref "X4") (pin "4") (pinfunction "KL_4") (pintype "passive"))
    )
    (net (code "47") (name "Net-(X6A-S)") (class "Default")
      (node (ref "Q5") (pin "5") (pinfunction "D_5") (pintype "passive"))
      (node (ref "Q5") (pin "6") (pinfunction "D_6") (pintype "passive"))
      (node (ref "Q5") (pin "7") (pinfunction "D_7") (pintype "passive"))
      (node (ref "Q5") (pin "8") (pinfunction "D_8") (pintype "passive"))
      (node (ref "X6") (pin "1") (pinfunction "S_1") (pintype "passive"))
    )
    (net (code "48") (name "Net-(X7-A)") (class "Default")
      (node (ref "R17") (pin "2") (pinfunction "2_2") (pintype "passive"))
      (node (ref "X7") (pin "A1") (pinfunction "A_A1") (pintype "passive"))
    )
    (net (code "49") (name "Net-(X7-A1)") (class "Default")
      (node (ref "R20") (pin "2") (pinfunction "2_2") (pintype "passive"))
      (node (ref "X7") (pin "A2") (pinfunction "A1_A2") (pintype "passive"))
    )
    (net (code "50") (name "R+12V") (class "Default")
      (node (ref "R13") (pin "2") (pinfunction "2_2") (pintype "passive"))
      (node (ref "R7") (pin "2") (pinfunction "2_2") (pintype "passive"))
      (node (ref "X4") (pin "1") (pinfunction "KL_1") (pintype "passive"))
      (node (ref "X4") (pin "2") (pinfunction "KL_2") (pintype "passive"))
      (node (ref "X4") (pin "5") (pinfunction "KL_5") (pintype "passive"))
      (node (ref "X4") (pin "7") (pinfunction "KL_7") (pintype "passive"))
    )
    (net (code "51") (name "RALI") (class "Default")
      (node (ref "OK2") (pin "8") (pinfunction "COL_8") (pintype "passive"))
      (node (ref "R7") (pin "1") (pinfunction "1_1") (pintype "passive"))
      (node (ref "X4") (pin "6") (pinfunction "KL_6") (pintype "passive"))
    )
    (net (code "52") (name "RALI_CTRL") (class "Default")
      (node (ref "A1") (pin "23") (pinfunction "P$23_23") (pintype "bidirectional"))
      (node (ref "R5") (pin "1") (pinfunction "1_1") (pintype "passive"))
    )
    (net (code "53") (name "RBLI") (class "Default")
      (node (ref "OK2") (pin "6") (pinfunction "COL_6") (pintype "passive"))
      (node (ref "R13") (pin "1") (pinfunction "1_1") (pintype "passive"))
      (node (ref "X4") (pin "8") (pinfunction "KL_8") (pintype "passive"))
    )
    (net (code "54") (name "RBLI_CTRL") (class "Default")
      (node (ref "A1") (pin "24") (pinfunction "P$24_24") (pintype "bidirectional"))
      (node (ref "R10") (pin "1") (pinfunction "1_1") (pintype "passive"))
    )
    (net (code "55") (name "RD_N") (class "Default")
      (node (ref "A1") (pin "36") (pinfunction "P$36_36") (pintype "bidirectional"))
      (node (ref "X7") (pin "6") (pinfunction "RD-_6") (pintype "passive"))
    )
    (net (code "56") (name "RD_P") (class "Default")
      (node (ref "A1") (pin "35") (pinfunction "P$35_35") (pintype "bidirectional"))
      (node (ref "X7") (pin "4") (pinfunction "RD+_4") (pintype "passive"))
    )
    (net (code "57") (name "REA") (class "Default")
      (node (ref "U2") (pin "14") (pinfunction "B2_14") (pintype "bidirectional"))
      (node (ref "X2") (pin "3") (pinfunction "S_3") (pintype "passive"))
    )
    (net (code "58") (name "REA3") (class "Default")
      (node (ref "A1") (pin "28") (pinfunction "P$28_28") (pintype "bidirectional"))
      (node (ref "U2") (pin "3") (pinfunction "A2_3") (pintype "bidirectional"))
    )
    (net (code "59") (name "REB") (class "Default")
      (node (ref "U2") (pin "13") (pinfunction "B3_13") (pintype "bidirectional"))
      (node (ref "X2") (pin "5") (pinfunction "S_5") (pintype "passive"))
    )
    (net (code "60") (name "REB3") (class "Default")
      (node (ref "A1") (pin "27") (pinfunction "P$27_27") (pintype "bidirectional"))
      (node (ref "U2") (pin "4") (pinfunction "A3_4") (pintype "bidirectional"))
    )
    (net (code "61") (name "RED_3V3") (class "Default")
      (node (ref "A1") (pin "14") (pinfunction "P$14_14") (pintype "bidirectional"))
      (node (ref "U6") (pin "4") (pinfunction "IN_B_4") (pintype "bidirectional"))
    )
    (net (code "62") (name "RED_OUT") (class "Default")
      (node (ref "J1") (pin "3") (pinfunction "3_3") (pintype "passive"))
      (node (ref "U6") (pin "5") (pinfunction "~{OUT_B}_5") (pintype "bidirectional"))
    )
    (net (code "63") (name "RGND") (class "Default")
      (node (ref "OK2") (pin "5") (pinfunction "EMIT_5") (pintype "passive"))
      (node (ref "OK2") (pin "7") (pinfunction "EMIT_7") (pintype "passive"))
      (node (ref "R15") (pin "1") (pinfunction "1_1") (pintype "passive"))
      (node (ref "X4") (pin "10") (pinfunction "KL_10") (pintype "passive"))
      (node (ref "X4") (pin "9") (pinfunction "KL_9") (pintype "passive"))
    )
    (net (code "64") (name "SAFETY_LIGHT") (class "Default")
      (node (ref "R25") (pin "1") (pinfunction "1_1") (pintype "passive"))
      (node (ref "U7") (pin "5") (pinfunction "~{OUT_B}_5") (pintype "bidirectional"))
    )
    (net (code "65") (name "SAFETY_LIGHT_3V3") (class "Default")
      (node (ref "A1") (pin "12") (pinfunction "P$12_12") (pintype "bidirectional"))
      (node (ref "U7") (pin "4") (pinfunction "IN_B_4") (pintype "bidirectional"))
    )
    (net (code "66") (name "SCL") (class "Default")
      (node (ref "A1") (pin "10") (pinfunction "P$10_10") (pintype "bidirectional"))
      (node (ref "R8") (pin "1") (pinfunction "1_1") (pintype "passive"))
      (node (ref "U1") (pin "23") (pinfunction "SCL/SCLK_23") (pintype "bidirectional"))
    )
    (net (code "67") (name "SDA") (class "Default")
      (node (ref "A1") (pin "9") (pinfunction "P$9_9") (pintype "bidirectional"))
      (node (ref "R11") (pin "1") (pinfunction "1_1") (pintype "passive"))
      (node (ref "U1") (pin "24") (pinfunction "SDA/SDI_24") (pintype "bidirectional"))
    )
    (net (code "68") (name "TD_N") (class "Default")
      (node (ref "A1") (pin "34") (pinfunction "P$34_34") (pintype "bidirectional"))
      (node (ref "X7") (pin "3") (pinfunction "TD-_3") (pintype "passive"))
    )
    (net (code "69") (name "TD_P") (class "Default")
      (node (ref "A1") (pin "33") (pinfunction "P$33_33") (pintype "bidirectional"))
      (node (ref "X7") (pin "1") (pinfunction "TD+_1") (pintype "passive"))
    )
    (net (code "70") (name "unconnected-(A1-P$3-Pad3)") (class "Default")
      (node (ref "A1") (pin "3") (pinfunction "P$3_3") (pintype "bidirectional"))
    )
    (net (code "71") (name "unconnected-(A1-P$4-Pad4)") (class "Default")
      (node (ref "A1") (pin "4") (pinfunction "P$4_4") (pintype "bidirectional"))
    )
    (net (code "72") (name "unconnected-(A1-P$5-Pad5)") (class "Default")
      (node (ref "A1") (pin "5") (pinfunction "P$5_5") (pintype "bidirectional"))
    )
    (net (code "73") (name "unconnected-(A1-P$6-Pad6)") (class "Default")
      (node (ref "A1") (pin "6") (pinfunction "P$6_6") (pintype "bidirectional"))
    )
    (net (code "74") (name "unconnected-(A1-P$7-Pad7)") (class "Default")
      (node (ref "A1") (pin "7") (pinfunction "P$7_7") (pintype "bidirectional"))
    )
    (net (code "75") (name "unconnected-(A1-P$19-Pad19)") (class "Default")
      (node (ref "A1") (pin "19") (pinfunction "P$19_19") (pintype "bidirectional"))
    )
    (net (code "76") (name "unconnected-(A1-P$37-Pad37)") (class "Default")
      (node (ref "A1") (pin "37") (pinfunction "P$37_37") (pintype "bidirectional"))
    )
    (net (code "77") (name "unconnected-(A1-P$38-Pad38)") (class "Default")
      (node (ref "A1") (pin "38") (pinfunction "P$38_38") (pintype "bidirectional"))
    )
    (net (code "78") (name "unconnected-(J1-Pad7)") (class "Default")
      (node (ref "J1") (pin "7") (pinfunction "7_7") (pintype "passive"))
    )
    (net (code "79") (name "unconnected-(J1-Pad8)") (class "Default")
      (node (ref "J1") (pin "8") (pinfunction "8_8") (pintype "passive"))
    )
    (net (code "80") (name "unconnected-(J1-Pad9)") (class "Default")
      (node (ref "J1") (pin "9") (pinfunction "9_9") (pintype "passive"))
    )
    (net (code "81") (name "unconnected-(U1-AUX_CL-Pad7)") (class "Default")
      (node (ref "U1") (pin "7") (pinfunction "AUX_CL_7") (pintype "bidirectional"))
    )
    (net (code "82") (name "unconnected-(U1-AUX_DA-Pad21)") (class "Default")
      (node (ref "U1") (pin "21") (pinfunction "AUX_DA_21") (pintype "bidirectional"))
    )
    (net (code "83") (name "unconnected-(U2-A6-Pad7)") (class "Default")
      (node (ref "U2") (pin "7") (pinfunction "A6_7") (pintype "bidirectional"))
    )
    (net (code "84") (name "unconnected-(U2-B6-Pad10)") (class "Default")
      (node (ref "U2") (pin "10") (pinfunction "B6_10") (pintype "bidirectional"))
    )
    (net (code "85") (name "unconnected-(U5-NC-Pad1)") (class "Default")
      (node (ref "U5") (pin "1") (pinfunction "NC_1") (pintype "bidirectional"))
    )
    (net (code "86") (name "unconnected-(U5-NC2-Pad8)") (class "Default")
      (node (ref "U5") (pin "8") (pinfunction "NC2_8") (pintype "bidirectional"))
    )
    (net (code "87") (name "unconnected-(U6-NC-Pad1)") (class "Default")
      (node (ref "U6") (pin "1") (pinfunction "NC_1") (pintype "bidirectional"))
    )
    (net (code "88") (name "unconnected-(U6-NC2-Pad8)") (class "Default")
      (node (ref "U6") (pin "8") (pinfunction "NC2_8") (pintype "bidirectional"))
    )
    (net (code "89") (name "unconnected-(U7-IN_A-Pad2)") (class "Default")
      (node (ref "U7") (pin "2") (pinfunction "IN_A_2") (pintype "bidirectional"))
    )
    (net (code "90") (name "unconnected-(U7-NC-Pad1)") (class "Default")
      (node (ref "U7") (pin "1") (pinfunction "NC_1") (pintype "bidirectional"))
    )
    (net (code "91") (name "unconnected-(U7-NC2-Pad8)") (class "Default")
      (node (ref "U7") (pin "8") (pinfunction "NC2_8") (pintype "bidirectional"))
    )
    (net (code "92") (name "unconnected-(U7-~{OUT_A}-Pad7)") (class "Default")
      (node (ref "U7") (pin "7") (pinfunction "~{OUT_A}_7") (pintype "bidirectional"))
    )
    (net (code "93") (name "unconnected-(X1-Pad4)") (class "Default")
      (node (ref "X1") (pin "4") (pinfunction "4_4") (pintype "passive"))
    )
    (net (code "94") (name "unconnected-(X2B-S-Pad2)") (class "Default")
      (node (ref "X2") (pin "2") (pinfunction "S_2") (pintype "passive"))
    )
    (net (code "95") (name "unconnected-(X3D-KL-Pad3)") (class "Default")
      (node (ref "X3") (pin "3") (pinfunction "KL_3") (pintype "passive"))
    )
    (net (code "96") (name "unconnected-(X4D-KL-Pad3)") (class "Default")
      (node (ref "X4") (pin "3") (pinfunction "KL_3") (pintype "passive"))
    )
    (net (code "97") (name "unconnected-(X5B-S-Pad2)") (class "Default")
      (node (ref "X5") (pin "2") (pinfunction "S_2") (pintype "passive"))
    )
    (net (code "98") (name "unconnected-(X7-C_GND-Pad8)") (class "Default")
      (node (ref "X7") (pin "8") (pinfunction "C_GND_8") (pintype "passive"))
    )
    (net (code "99") (name "unconnected-(X7-NC-Pad7)") (class "Default")
      (node (ref "X7") (pin "7") (pinfunction "NC_7") (pintype "passive"))
    )
  )
)
